# IsoUSBTest.net
KiCad netlist of a schematic drawn in Altium Designer
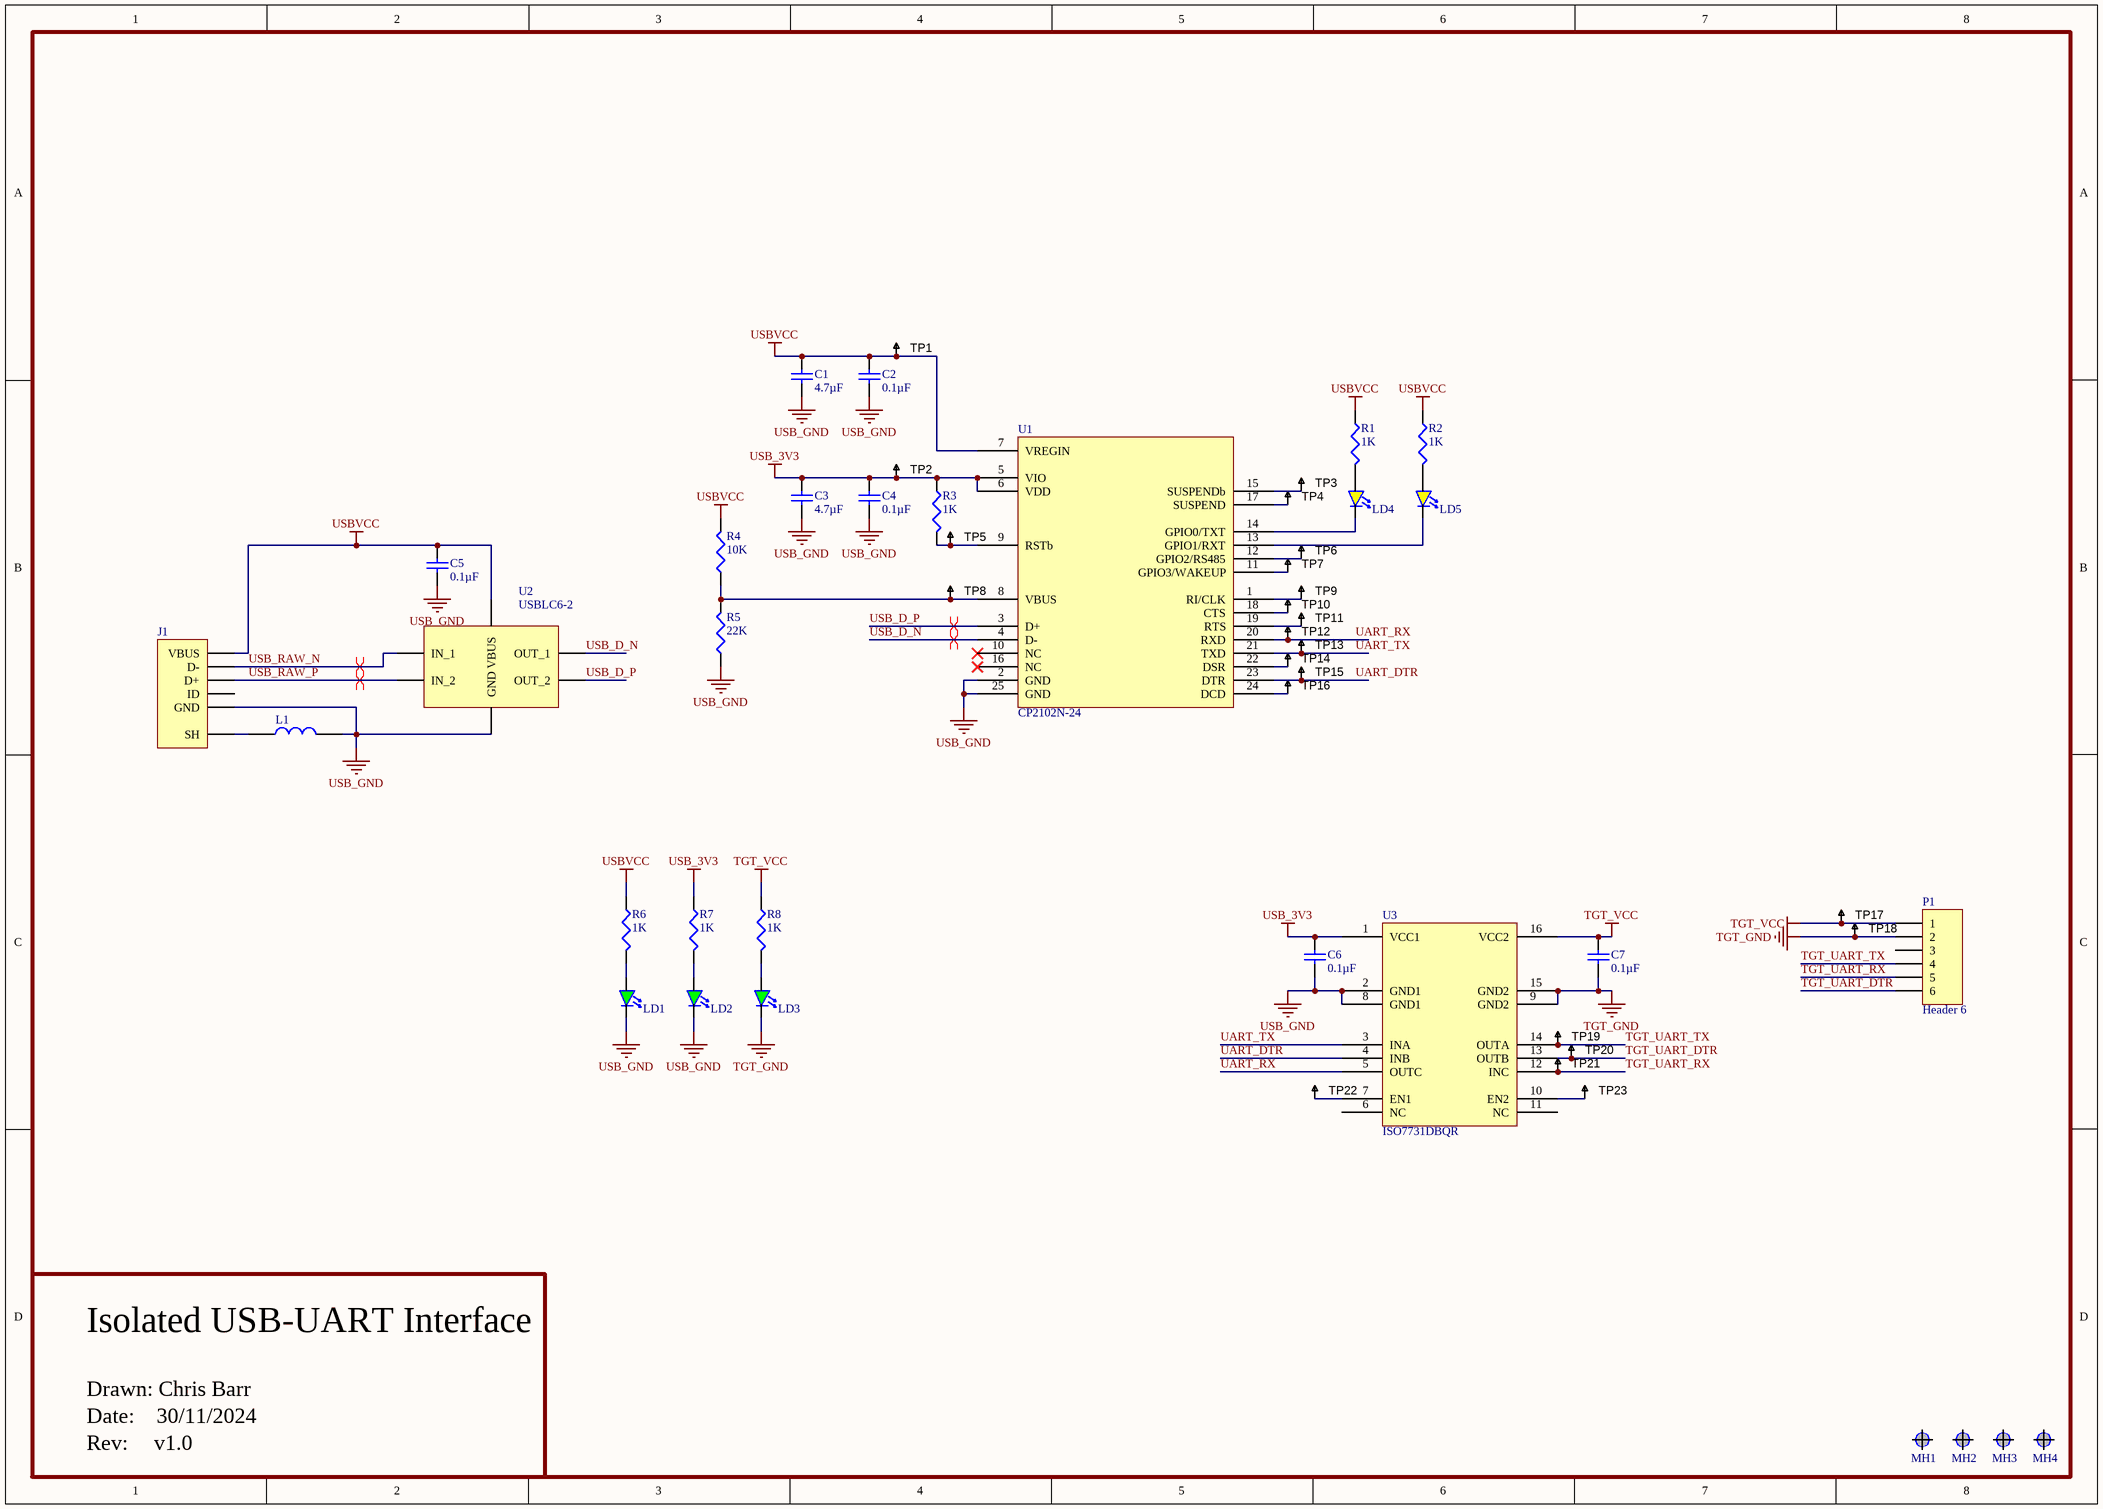
[diagram p0: IsoUSBTest.SchDoc]

(export (version "E")
  (design (tool "Eeschema 10.0.6"))
  (components
    (comp (ref "C1")
      (value "4.7µF")
      (footprint "CAPC1608X90N")
      (description "CAP CER 4.7UF 16V X5R 0603")
      (fields (field (name "VOLTAGE") "16V") (field (name "TOLERANCE") "±10%"))
      (libsource (lib "Ceramic Cap DBLIB") (part "Capacitor"))
    )
    (comp (ref "C2")
      (value "0.1µF")
      (footprint "CAPC1608X90N")
      (description "CAP CER 0.1UF 16V X7R 0603")
      (fields (field (name "VOLTAGE") "16V") (field (name "TOLERANCE") "±10%"))
      (libsource (lib "Ceramic Cap DBLIB") (part "Capacitor"))
    )
    (comp (ref "C3")
      (value "4.7µF")
      (footprint "CAPC1608X90N")
      (description "CAP CER 4.7UF 16V X5R 0603")
      (fields (field (name "VOLTAGE") "16V") (field (name "TOLERANCE") "±10%"))
      (libsource (lib "Ceramic Cap DBLIB") (part "Capacitor"))
    )
    (comp (ref "C4")
      (value "0.1µF")
      (footprint "CAPC1608X90N")
      (description "CAP CER 0.1UF 16V X7R 0603")
      (fields (field (name "VOLTAGE") "16V") (field (name "TOLERANCE") "±10%"))
      (libsource (lib "Ceramic Cap DBLIB") (part "Capacitor"))
    )
    (comp (ref "C5")
      (value "0.1µF")
      (footprint "CAPC1608X90N")
      (description "CAP CER 0.1UF 16V X7R 0603")
      (fields (field (name "VOLTAGE") "16V") (field (name "TOLERANCE") "±10%"))
      (libsource (lib "Ceramic Cap DBLIB") (part "Capacitor"))
    )
    (comp (ref "C6")
      (value "0.1µF")
      (footprint "CAPC1608X90N")
      (description "CAP CER 0.1UF 16V X7R 0603")
      (fields (field (name "VOLTAGE") "16V") (field (name "TOLERANCE") "±10%"))
      (libsource (lib "Ceramic Cap DBLIB") (part "Capacitor"))
    )
    (comp (ref "C7")
      (value "0.1µF")
      (footprint "CAPC1608X90N")
      (description "CAP CER 0.1UF 16V X7R 0603")
      (fields (field (name "VOLTAGE") "16V") (field (name "TOLERANCE") "±10%"))
      (libsource (lib "Ceramic Cap DBLIB") (part "Capacitor"))
    )
    (comp (ref "J1")
      (value "~")
      (footprint "Micro-USB B Molex 105017-0001")
      (description "CONN RCPT USB2.0 MICRO B SMD R/A")
      (libsource (lib "picoprint_library") (part "Micro-USB B Socket"))
    )
    (comp (ref "L1")
      (value "~")
      (footprint "Res 2012-0805")
      (description "FERRITE BEAD 220 OHM 0805 1LN")
      (libsource (lib "RUMBA_v2") (part "Ferrite Bead SMD 0805"))
    )
    (comp (ref "LD1")
      (value "LEDG  0603")
      (footprint "LED 1608-0603")
      (description "LED GREEN CLEAR CHIP SMD 0603")
      (libsource (lib "main_library") (part "LEDG  0603"))
    )
    (comp (ref "LD2")
      (value "LEDG  0603")
      (footprint "LED 1608-0603")
      (description "LED GREEN CLEAR CHIP SMD 0603")
      (libsource (lib "main_library") (part "LEDG  0603"))
    )
    (comp (ref "LD3")
      (value "LEDG  0603")
      (footprint "LED 1608-0603")
      (description "LED GREEN CLEAR CHIP SMD 0603")
      (libsource (lib "main_library") (part "LEDG  0603"))
    )
    (comp (ref "LD4")
      (value "~")
      (footprint "LED 1608-0603")
      (description "LED YELLOW CLEAR CHIP SMD 0603")
      (libsource (lib "picoprint_library") (part "LEDY  0603"))
    )
    (comp (ref "LD5")
      (value "~")
      (footprint "LED 1608-0603")
      (description "LED YELLOW CLEAR CHIP SMD 0603")
      (libsource (lib "picoprint_library") (part "LEDY  0603"))
    )
    (comp (ref "MH1")
      (value "Screw Hole")
      (footprint "M3-Hole-2")
      (libsource (lib "main_library") (part "Screw Hole"))
    )
    (comp (ref "MH2")
      (value "Screw Hole")
      (footprint "M3-Hole-2")
      (libsource (lib "main_library") (part "Screw Hole"))
    )
    (comp (ref "MH3")
      (value "Screw Hole")
      (footprint "M3-Hole-2")
      (libsource (lib "main_library") (part "Screw Hole"))
    )
    (comp (ref "MH4")
      (value "Screw Hole")
      (footprint "M3-Hole-2")
      (libsource (lib "main_library") (part "Screw Hole"))
    )
    (comp (ref "P1")
      (value "Header 6")
      (footprint "HDR1X6-HEADER")
      (description "Header, 6-Pin")
      (libsource (lib "main_library") (part "Header 1X6"))
    )
    (comp (ref "R1")
      (value "1K")
      (footprint "RES 1608-0603")
      (description "RES SMD 1K OHM 1% 1/10W 0603")
      (fields (field (name "PUBLISHER") "Altium Limited"))
      (libsource (lib "RUMBA_v2") (part "Res-0603-1K"))
    )
    (comp (ref "R2")
      (value "1K")
      (footprint "RES 1608-0603")
      (description "RES SMD 1K OHM 1% 1/10W 0603")
      (fields (field (name "PUBLISHER") "Altium Limited"))
      (libsource (lib "RUMBA_v2") (part "Res-0603-1K"))
    )
    (comp (ref "R3")
      (value "1K")
      (footprint "RES 1608-0603")
      (description "RES SMD 1K OHM 1% 1/10W 0603")
      (fields (field (name "PUBLISHER") "Altium Limited"))
      (libsource (lib "RUMBA_v2") (part "Res-0603-1K"))
    )
    (comp (ref "R4")
      (value "10K")
      (footprint "RES 1608-0603")
      (description "RES SMD 10K OHM 1% 1/10W 0603")
      (fields (field (name "PUBLISHER") "Altium Limited"))
      (libsource (lib "RUMBA_v2") (part "Res-0603-10K"))
    )
    (comp (ref "R5")
      (value "22K")
      (footprint "RES 1608-0603")
      (description "RES SMD 22K OHM 1% 1/10W 0603")
      (fields (field (name "PUBLISHER") "Altium Limited"))
      (libsource (lib "RUMBA_v2") (part "Res-0603-10K"))
    )
    (comp (ref "R6")
      (value "1K")
      (footprint "RES 1608-0603")
      (description "RES SMD 1K OHM 1% 1/10W 0603")
      (fields (field (name "PUBLISHER") "Altium Limited"))
      (libsource (lib "RUMBA_v2") (part "Res-0603-1K"))
    )
    (comp (ref "R7")
      (value "1K")
      (footprint "RES 1608-0603")
      (description "RES SMD 1K OHM 1% 1/10W 0603")
      (fields (field (name "PUBLISHER") "Altium Limited"))
      (libsource (lib "RUMBA_v2") (part "Res-0603-1K"))
    )
    (comp (ref "R8")
      (value "1K")
      (footprint "RES 1608-0603")
      (description "RES SMD 1K OHM 1% 1/10W 0603")
      (fields (field (name "PUBLISHER") "Altium Limited"))
      (libsource (lib "RUMBA_v2") (part "Res-0603-1K"))
    )
    (comp (ref "TP1")
      (value "TESTPOINT")
      (footprint "TP-THT_TINY")
      (description "SMD test pin")
      (libsource (lib "PBL - Test Points") (part "TESTPOINT"))
    )
    (comp (ref "TP2")
      (value "TESTPOINT")
      (footprint "TP-THT_TINY")
      (description "SMD test pin")
      (libsource (lib "PBL - Test Points") (part "TESTPOINT"))
    )
    (comp (ref "TP3")
      (value "TESTPOINT")
      (footprint "TP-THT_TINY")
      (description "SMD test pin")
      (libsource (lib "PBL - Test Points") (part "TESTPOINT"))
    )
    (comp (ref "TP4")
      (value "TESTPOINT")
      (footprint "TP-THT_TINY")
      (description "SMD test pin")
      (libsource (lib "PBL - Test Points") (part "TESTPOINT"))
    )
    (comp (ref "TP5")
      (value "TESTPOINT")
      (footprint "TP-THT_TINY")
      (description "SMD test pin")
      (libsource (lib "PBL - Test Points") (part "TESTPOINT"))
    )
    (comp (ref "TP6")
      (value "TESTPOINT")
      (footprint "TP-THT_TINY")
      (description "SMD test pin")
      (libsource (lib "PBL - Test Points") (part "TESTPOINT"))
    )
    (comp (ref "TP7")
      (value "TESTPOINT")
      (footprint "TP-THT_TINY")
      (description "SMD test pin")
      (libsource (lib "PBL - Test Points") (part "TESTPOINT"))
    )
    (comp (ref "TP8")
      (value "TESTPOINT")
      (footprint "TP-THT_TINY")
      (description "SMD test pin")
      (libsource (lib "PBL - Test Points") (part "TESTPOINT"))
    )
    (comp (ref "TP9")
      (value "TESTPOINT")
      (footprint "TP-THT_TINY")
      (description "SMD test pin")
      (libsource (lib "PBL - Test Points") (part "TESTPOINT"))
    )
    (comp (ref "TP10")
      (value "TESTPOINT")
      (footprint "TP-THT_TINY")
      (description "SMD test pin")
      (libsource (lib "PBL - Test Points") (part "TESTPOINT"))
    )
    (comp (ref "TP11")
      (value "TESTPOINT")
      (footprint "TP-THT_TINY")
      (description "SMD test pin")
      (libsource (lib "PBL - Test Points") (part "TESTPOINT"))
    )
    (comp (ref "TP12")
      (value "TESTPOINT")
      (footprint "TP-THT_TINY")
      (description "SMD test pin")
      (libsource (lib "PBL - Test Points") (part "TESTPOINT"))
    )
    (comp (ref "TP13")
      (value "TESTPOINT")
      (footprint "TP-THT_TINY")
      (description "SMD test pin")
      (libsource (lib "PBL - Test Points") (part "TESTPOINT"))
    )
    (comp (ref "TP14")
      (value "TESTPOINT")
      (footprint "TP-THT_TINY")
      (description "SMD test pin")
      (libsource (lib "PBL - Test Points") (part "TESTPOINT"))
    )
    (comp (ref "TP15")
      (value "TESTPOINT")
      (footprint "TP-THT_TINY")
      (description "SMD test pin")
      (libsource (lib "PBL - Test Points") (part "TESTPOINT"))
    )
    (comp (ref "TP16")
      (value "TESTPOINT")
      (footprint "TP-THT_TINY")
      (description "SMD test pin")
      (libsource (lib "PBL - Test Points") (part "TESTPOINT"))
    )
    (comp (ref "TP17")
      (value "TESTPOINT")
      (footprint "TP-THT_TINY")
      (description "SMD test pin")
      (libsource (lib "PBL - Test Points") (part "TESTPOINT"))
    )
    (comp (ref "TP18")
      (value "TESTPOINT")
      (footprint "TP-THT_TINY")
      (description "SMD test pin")
      (libsource (lib "PBL - Test Points") (part "TESTPOINT"))
    )
    (comp (ref "TP19")
      (value "TESTPOINT")
      (footprint "TP-THT_TINY")
      (description "SMD test pin")
      (libsource (lib "PBL - Test Points") (part "TESTPOINT"))
    )
    (comp (ref "TP20")
      (value "TESTPOINT")
      (footprint "TP-THT_TINY")
      (description "SMD test pin")
      (libsource (lib "PBL - Test Points") (part "TESTPOINT"))
    )
    (comp (ref "TP21")
      (value "TESTPOINT")
      (footprint "TP-THT_TINY")
      (description "SMD test pin")
      (libsource (lib "PBL - Test Points") (part "TESTPOINT"))
    )
    (comp (ref "TP22")
      (value "TESTPOINT")
      (footprint "TP-THT_TINY")
      (description "SMD test pin")
      (libsource (lib "PBL - Test Points") (part "TESTPOINT"))
    )
    (comp (ref "TP23")
      (value "TESTPOINT")
      (footprint "TP-THT_TINY")
      (description "SMD test pin")
      (libsource (lib "PBL - Test Points") (part "TESTPOINT"))
    )
    (comp (ref "U1")
      (value "CP2102N-24")
      (footprint "QFN50P400X400X80_HS-25N")
      (libsource (lib "main_library") (part "IC - CP2102N-24"))
    )
    (comp (ref "U2")
      (value "USBLC6-2")
      (footprint "SOT95P280X145-6N")
      (description "ESD Protection IC")
      (libsource (lib "main_library") (part "USBLC6-2 USB ESD Protection"))
    )
    (comp (ref "U3")
      (value "ISO7731DBQR")
      (footprint "SOP64P600X175-16N")
      (description "DGTL ISO 3000VRMS 3CH GP 16SSOP")
      (libsource (lib "main_library") (part "IC - TI ISO7731 Digital Isolator"))
    )
  )
  (nets
    (net (code "1") (name "/TGT_UART_DTR") (class "Default")
      (node (ref "P1") (pin "6") (pinfunction "6_6") (pintype "passive"))
      (node (ref "TP20") (pin "1") (pintype "passive"))
      (node (ref "U3") (pin "13") (pinfunction "OUTB_13") (pintype "passive"))
    )
    (net (code "2") (name "/TGT_UART_RX") (class "Default")
      (node (ref "P1") (pin "5") (pinfunction "5_5") (pintype "passive"))
      (node (ref "TP21") (pin "1") (pintype "passive"))
      (node (ref "U3") (pin "12") (pinfunction "INC_12") (pintype "passive"))
    )
    (net (code "3") (name "/TGT_UART_TX") (class "Default")
      (node (ref "P1") (pin "4") (pinfunction "4_4") (pintype "passive"))
      (node (ref "TP19") (pin "1") (pintype "passive"))
      (node (ref "U3") (pin "14") (pinfunction "OUTA_14") (pintype "passive"))
    )
    (net (code "4") (name "/UART_DTR") (class "Default")
      (node (ref "TP15") (pin "1") (pintype "passive"))
      (node (ref "U1") (pin "23") (pinfunction "DTR_23") (pintype "passive"))
      (node (ref "U3") (pin "4") (pinfunction "INB_4") (pintype "passive"))
    )
    (net (code "5") (name "/UART_RX") (class "Default")
      (node (ref "TP12") (pin "1") (pintype "passive"))
      (node (ref "U1") (pin "20") (pinfunction "RXD_20") (pintype "passive"))
      (node (ref "U3") (pin "5") (pinfunction "OUTC_5") (pintype "passive"))
    )
    (net (code "6") (name "/UART_TX") (class "Default")
      (node (ref "TP13") (pin "1") (pintype "passive"))
      (node (ref "U1") (pin "21") (pinfunction "TXD_21") (pintype "passive"))
      (node (ref "U3") (pin "3") (pinfunction "INA_3") (pintype "passive"))
    )
    (net (code "7") (name "/USB_D_N") (class "Default")
      (node (ref "U1") (pin "4") (pinfunction "D-_4") (pintype "passive"))
      (node (ref "U2") (pin "6") (pinfunction "OUT_1_6") (pintype "passive"))
    )
    (net (code "8") (name "/USB_D_P") (class "Default")
      (node (ref "U1") (pin "3") (pinfunction "D+_3") (pintype "passive"))
      (node (ref "U2") (pin "4") (pinfunction "OUT_2_4") (pintype "passive"))
    )
    (net (code "9") (name "/USB_RAW_N") (class "Default")
      (node (ref "J1") (pin "D-") (pinfunction "D-_D-") (pintype "passive"))
      (node (ref "U2") (pin "1") (pinfunction "IN_1_1") (pintype "passive"))
    )
    (net (code "10") (name "/USB_RAW_P") (class "Default")
      (node (ref "J1") (pin "D+") (pinfunction "D+_D+") (pintype "passive"))
      (node (ref "U2") (pin "3") (pinfunction "IN_2_3") (pintype "passive"))
    )
    (net (code "11") (name "Net-(J1-SH)") (class "Default")
      (node (ref "J1") (pin "SHIELD") (pinfunction "SH_SHIELD") (pintype "passive"))
      (node (ref "L1") (pin "1") (pinfunction "1_1") (pintype "passive"))
    )
    (net (code "12") (name "Net-(LD1-A)") (class "Default")
      (node (ref "LD1") (pin "1") (pinfunction "A_1") (pintype "passive"))
      (node (ref "R6") (pin "2") (pinfunction "2_2") (pintype "passive"))
    )
    (net (code "13") (name "Net-(LD2-A)") (class "Default")
      (node (ref "LD2") (pin "1") (pinfunction "A_1") (pintype "passive"))
      (node (ref "R7") (pin "2") (pinfunction "2_2") (pintype "passive"))
    )
    (net (code "14") (name "Net-(LD3-A)") (class "Default")
      (node (ref "LD3") (pin "1") (pinfunction "A_1") (pintype "passive"))
      (node (ref "R8") (pin "2") (pinfunction "2_2") (pintype "passive"))
    )
    (net (code "15") (name "Net-(LD4-A)") (class "Default")
      (node (ref "LD4") (pin "1") (pinfunction "A_1") (pintype "passive"))
      (node (ref "R1") (pin "2") (pinfunction "2_2") (pintype "passive"))
    )
    (net (code "16") (name "Net-(LD4-K)") (class "Default")
      (node (ref "LD4") (pin "2") (pinfunction "K_2") (pintype "passive"))
      (node (ref "U1") (pin "14") (pinfunction "GPIO0/TXT_14") (pintype "passive"))
    )
    (net (code "17") (name "Net-(LD5-A)") (class "Default")
      (node (ref "LD5") (pin "1") (pinfunction "A_1") (pintype "passive"))
      (node (ref "R2") (pin "2") (pinfunction "2_2") (pintype "passive"))
    )
    (net (code "18") (name "Net-(LD5-K)") (class "Default")
      (node (ref "LD5") (pin "2") (pinfunction "K_2") (pintype "passive"))
      (node (ref "U1") (pin "13") (pinfunction "GPIO1/RXT_13") (pintype "passive"))
    )
    (net (code "19") (name "Net-(U1-CTS)") (class "Default")
      (node (ref "TP10") (pin "1") (pintype "passive"))
      (node (ref "U1") (pin "18") (pinfunction "CTS_18") (pintype "passive"))
    )
    (net (code "20") (name "Net-(U1-DCD)") (class "Default")
      (node (ref "TP16") (pin "1") (pintype "passive"))
      (node (ref "U1") (pin "24") (pinfunction "DCD_24") (pintype "passive"))
    )
    (net (code "21") (name "Net-(U1-DSR)") (class "Default")
      (node (ref "TP14") (pin "1") (pintype "passive"))
      (node (ref "U1") (pin "22") (pinfunction "DSR_22") (pintype "passive"))
    )
    (net (code "22") (name "Net-(U1-GPIO2{slash}RS485)") (class "Default")
      (node (ref "TP6") (pin "1") (pintype "passive"))
      (node (ref "U1") (pin "12") (pinfunction "GPIO2/RS485_12") (pintype "passive"))
    )
    (net (code "23") (name "Net-(U1-GPIO3{slash}WAKEUP)") (class "Default")
      (node (ref "TP7") (pin "1") (pintype "passive"))
      (node (ref "U1") (pin "11") (pinfunction "GPIO3/WAKEUP_11") (pintype "passive"))
    )
    (net (code "24") (name "Net-(U1-RI{slash}CLK)") (class "Default")
      (node (ref "TP9") (pin "1") (pintype "passive"))
      (node (ref "U1") (pin "1") (pinfunction "RI/CLK_1") (pintype "passive"))
    )
    (net (code "25") (name "Net-(U1-RSTb)") (class "Default")
      (node (ref "R3") (pin "2") (pinfunction "2_2") (pintype "passive"))
      (node (ref "TP5") (pin "1") (pintype "passive"))
      (node (ref "U1") (pin "9") (pinfunction "RSTb_9") (pintype "passive"))
    )
    (net (code "26") (name "Net-(U1-RTS)") (class "Default")
      (node (ref "TP11") (pin "1") (pintype "passive"))
      (node (ref "U1") (pin "19") (pinfunction "RTS_19") (pintype "passive"))
    )
    (net (code "27") (name "Net-(U1-SUSPEND)") (class "Default")
      (node (ref "TP4") (pin "1") (pintype "passive"))
      (node (ref "U1") (pin "17") (pinfunction "SUSPEND_17") (pintype "passive"))
    )
    (net (code "28") (name "Net-(U1-SUSPENDb)") (class "Default")
      (node (ref "TP3") (pin "1") (pintype "passive"))
      (node (ref "U1") (pin "15") (pinfunction "SUSPENDb_15") (pintype "passive"))
    )
    (net (code "29") (name "Net-(U1-VBUS)") (class "Default")
      (node (ref "R4") (pin "1") (pinfunction "1_1") (pintype "passive"))
      (node (ref "R5") (pin "2") (pinfunction "2_2") (pintype "passive"))
      (node (ref "TP8") (pin "1") (pintype "passive"))
      (node (ref "U1") (pin "8") (pinfunction "VBUS_8") (pintype "passive"))
    )
    (net (code "30") (name "Net-(U3-EN1)") (class "Default")
      (node (ref "TP22") (pin "1") (pintype "passive"))
      (node (ref "U3") (pin "7") (pinfunction "EN1_7") (pintype "passive"))
    )
    (net (code "31") (name "Net-(U3-EN2)") (class "Default")
      (node (ref "TP23") (pin "1") (pintype "passive"))
      (node (ref "U3") (pin "10") (pinfunction "EN2_10") (pintype "passive"))
    )
    (net (code "32") (name "TGT_GND") (class "Default")
      (node (ref "C7") (pin "1") (pinfunction "1_1") (pintype "passive"))
      (node (ref "LD3") (pin "2") (pinfunction "K_2") (pintype "passive"))
      (node (ref "P1") (pin "2") (pinfunction "2_2") (pintype "passive"))
      (node (ref "TP18") (pin "1") (pintype "passive"))
      (node (ref "U3") (pin "15") (pinfunction "GND2_15") (pintype "passive"))
      (node (ref "U3") (pin "9") (pinfunction "GND2_9") (pintype "passive"))
    )
    (net (code "33") (name "TGT_VCC") (class "Default")
      (node (ref "C7") (pin "2") (pinfunction "2_2") (pintype "passive"))
      (node (ref "P1") (pin "1") (pinfunction "1_1") (pintype "passive"))
      (node (ref "R8") (pin "1") (pinfunction "1_1") (pintype "passive"))
      (node (ref "TP17") (pin "1") (pintype "passive"))
      (node (ref "U3") (pin "16") (pinfunction "VCC2_16") (pintype "passive"))
    )
    (net (code "34") (name "USBVCC") (class "Default")
      (node (ref "C1") (pin "2") (pinfunction "2_2") (pintype "passive"))
      (node (ref "C2") (pin "2") (pinfunction "2_2") (pintype "passive"))
      (node (ref "C5") (pin "2") (pinfunction "2_2") (pintype "passive"))
      (node (ref "J1") (pin "VBUS") (pinfunction "VBUS_VBUS") (pintype "passive"))
      (node (ref "R1") (pin "1") (pinfunction "1_1") (pintype "passive"))
      (node (ref "R2") (pin "1") (pinfunction "1_1") (pintype "passive"))
      (node (ref "R4") (pin "2") (pinfunction "2_2") (pintype "passive"))
      (node (ref "R6") (pin "1") (pinfunction "1_1") (pintype "passive"))
      (node (ref "TP1") (pin "1") (pintype "passive"))
      (node (ref "U1") (pin "7") (pinfunction "VREGIN_7") (pintype "passive"))
      (node (ref "U2") (pin "5") (pinfunction "VBUS_5") (pintype "passive"))
    )
    (net (code "35") (name "USB_3V3") (class "Default")
      (node (ref "C3") (pin "2") (pinfunction "2_2") (pintype "passive"))
      (node (ref "C4") (pin "2") (pinfunction "2_2") (pintype "passive"))
      (node (ref "C6") (pin "2") (pinfunction "2_2") (pintype "passive"))
      (node (ref "R3") (pin "1") (pinfunction "1_1") (pintype "passive"))
      (node (ref "R7") (pin "1") (pinfunction "1_1") (pintype "passive"))
      (node (ref "TP2") (pin "1") (pintype "passive"))
      (node (ref "U1") (pin "5") (pinfunction "VIO_5") (pintype "passive"))
      (node (ref "U1") (pin "6") (pinfunction "VDD_6") (pintype "passive"))
      (node (ref "U3") (pin "1") (pinfunction "VCC1_1") (pintype "passive"))
    )
    (net (code "36") (name "USB_GND") (class "Default")
      (node (ref "C1") (pin "1") (pinfunction "1_1") (pintype "passive"))
      (node (ref "C2") (pin "1") (pinfunction "1_1") (pintype "passive"))
      (node (ref "C3") (pin "1") (pinfunction "1_1") (pintype "passive"))
      (node (ref "C4") (pin "1") (pinfunction "1_1") (pintype "passive"))
      (node (ref "C5") (pin "1") (pinfunction "1_1") (pintype "passive"))
      (node (ref "C6") (pin "1") (pinfunction "1_1") (pintype "passive"))
      (node (ref "J1") (pin "GND") (pinfunction "GND_GND") (pintype "passive"))
      (node (ref "L1") (pin "2") (pinfunction "2_2") (pintype "passive"))
      (node (ref "LD1") (pin "2") (pinfunction "K_2") (pintype "passive"))
      (node (ref "LD2") (pin "2") (pinfunction "K_2") (pintype "passive"))
      (node (ref "R5") (pin "1") (pinfunction "1_1") (pintype "passive"))
      (node (ref "U1") (pin "2") (pinfunction "GND_2") (pintype "passive"))
      (node (ref "U1") (pin "25") (pinfunction "GND_25") (pintype "passive"))
      (node (ref "U2") (pin "2") (pinfunction "GND_2") (pintype "passive"))
      (node (ref "U3") (pin "2") (pinfunction "GND1_2") (pintype "passive"))
      (node (ref "U3") (pin "8") (pinfunction "GND1_8") (pintype "passive"))
    )
    (net (code "37") (name "unconnected-(J1-PadID)") (class "Default")
      (node (ref "J1") (pin "ID") (pinfunction "ID_ID") (pintype "passive"))
    )
    (net (code "38") (name "unconnected-(MH1-0-PadM3)") (class "Default")
      (node (ref "MH1") (pin "M3") (pinfunction "0_M3") (pintype "passive"))
    )
    (net (code "39") (name "unconnected-(MH2-0-PadM3)") (class "Default")
      (node (ref "MH2") (pin "M3") (pinfunction "0_M3") (pintype "passive"))
    )
    (net (code "40") (name "unconnected-(MH3-0-PadM3)") (class "Default")
      (node (ref "MH3") (pin "M3") (pinfunction "0_M3") (pintype "passive"))
    )
    (net (code "41") (name "unconnected-(MH4-0-PadM3)") (class "Default")
      (node (ref "MH4") (pin "M3") (pinfunction "0_M3") (pintype "passive"))
    )
    (net (code "42") (name "unconnected-(P1-Pad3)") (class "Default")
      (node (ref "P1") (pin "3") (pinfunction "3_3") (pintype "passive"))
    )
    (net (code "43") (name "unconnected-(U1-NC-Pad10)") (class "Default")
      (node (ref "U1") (pin "10") (pinfunction "NC_10") (pintype "passive+no_connect"))
    )
    (net (code "44") (name "unconnected-(U1-NC-Pad16)") (class "Default")
      (node (ref "U1") (pin "16") (pinfunction "NC_16") (pintype "passive+no_connect"))
    )
    (net (code "45") (name "unconnected-(U3-NC-Pad6)") (class "Default")
      (node (ref "U3") (pin "6") (pinfunction "NC_6") (pintype "passive"))
    )
    (net (code "46") (name "unconnected-(U3-NC-Pad11)") (class "Default")
      (node (ref "U3") (pin "11") (pinfunction "NC_11") (pintype "passive"))
    )
  )
)
